# Scale_junction_board.net
KiCad netlist of a schematic drawn in EAGLE
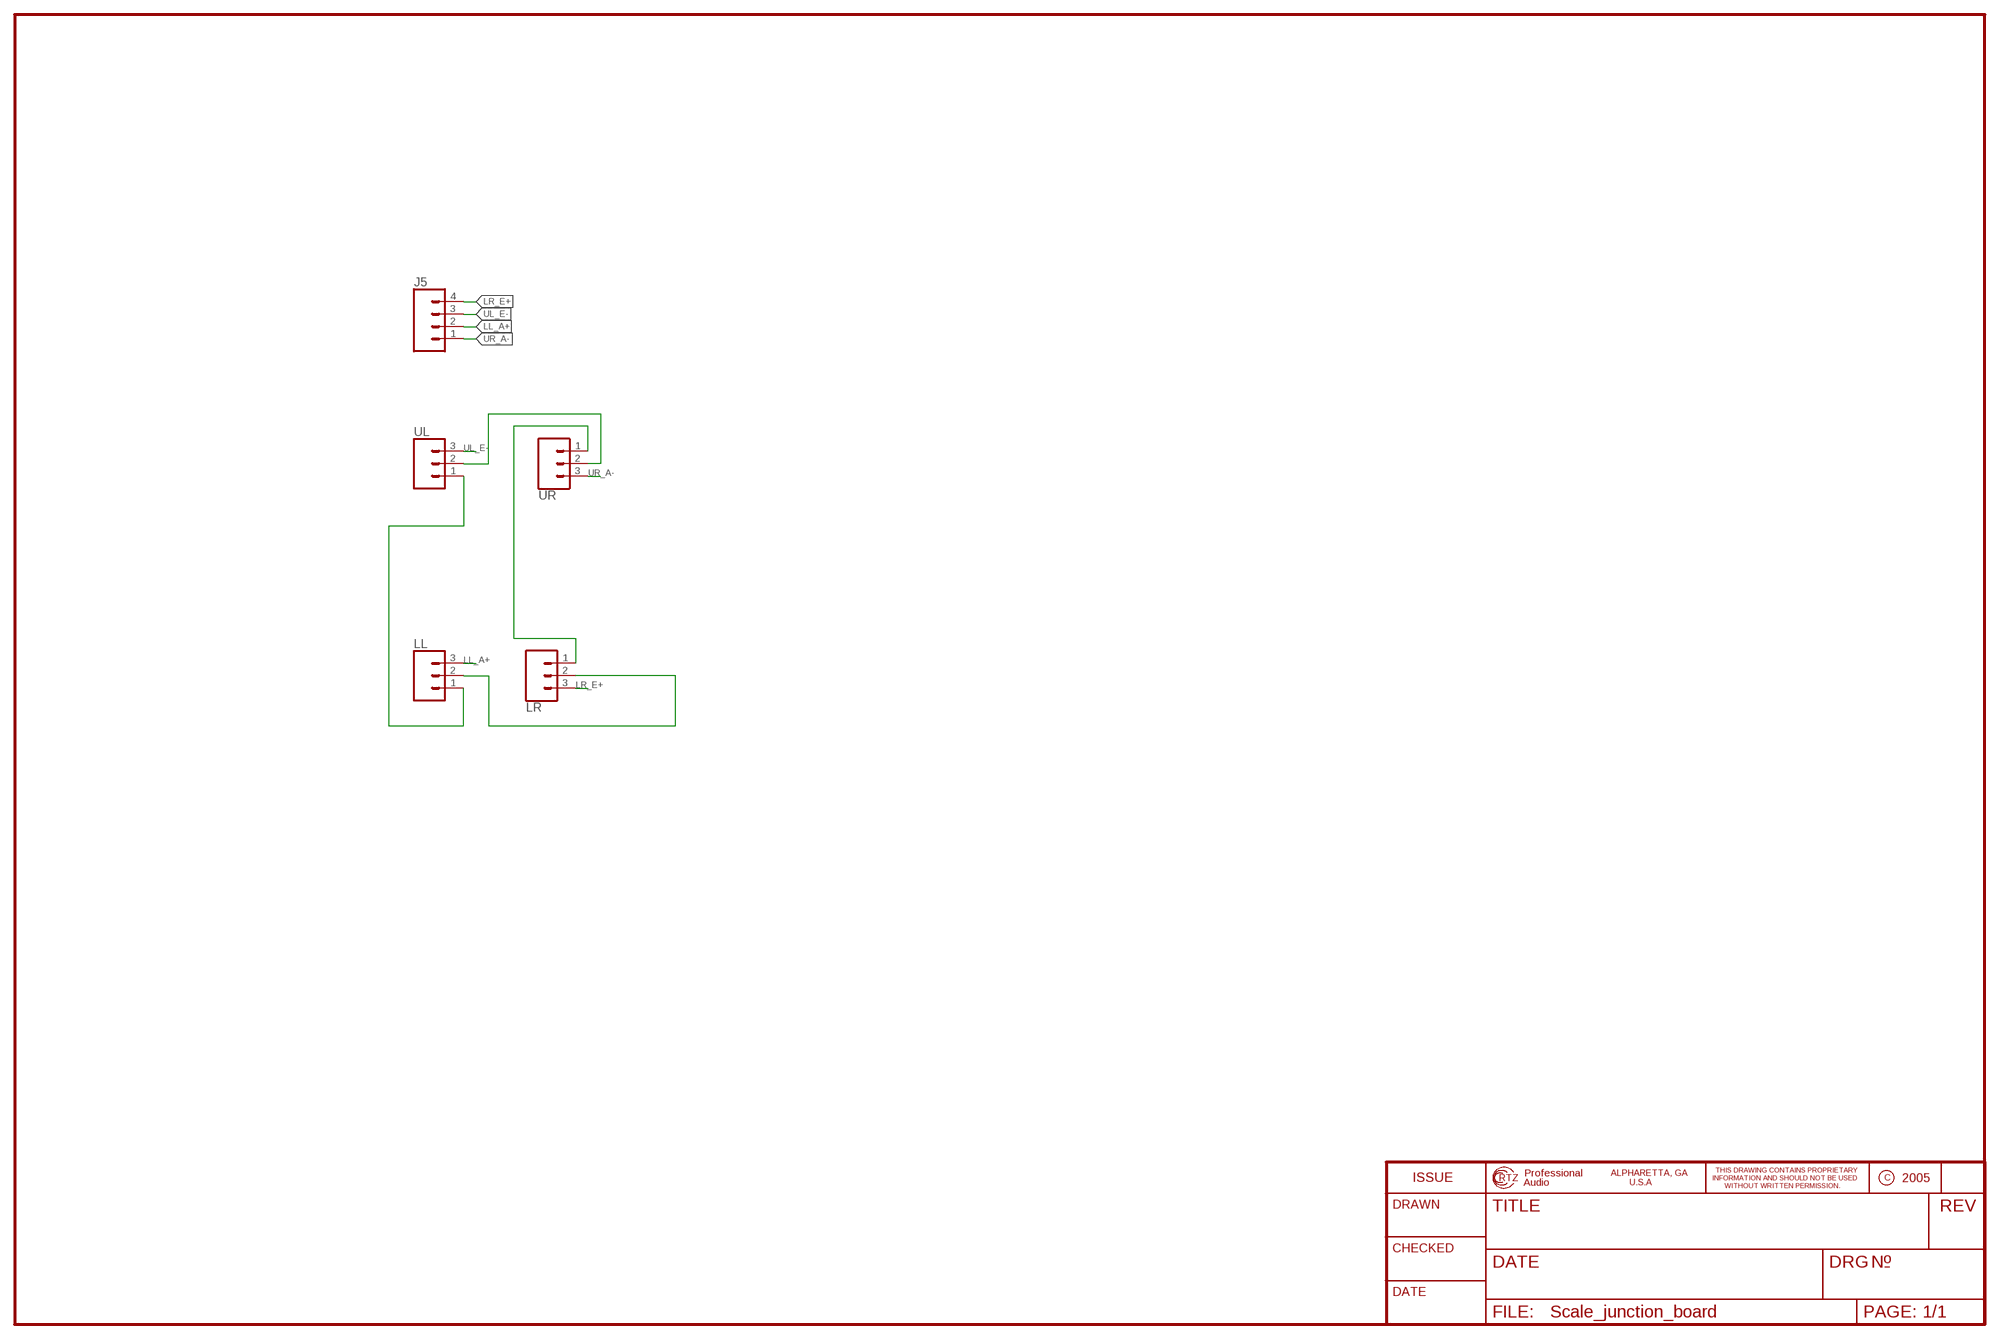
[diagram p0: schematic, sheet 1]

(export (version "E")
  (design (tool "Eeschema 10.0.6"))
  (components
    (comp (ref "J5")
      (value "CONN_04LONGPADS")
      (footprint "eagle-import:1X04_LONGPADS")
      (libsource (lib "eagle-import") (part "CONN_04LONGPADS"))
    )
    (comp (ref "LL")
      (value "CONN_03LONGPADS")
      (footprint "eagle-import:1X03_LONGPADS")
      (libsource (lib "eagle-import") (part "CONN_03LONGPADS"))
    )
    (comp (ref "LR")
      (value "CONN_03LONGPADS")
      (footprint "eagle-import:1X03_LONGPADS")
      (libsource (lib "eagle-import") (part "CONN_03LONGPADS"))
    )
    (comp (ref "UL")
      (value "CONN_03LONGPADS")
      (footprint "eagle-import:1X03_LONGPADS")
      (libsource (lib "eagle-import") (part "CONN_03LONGPADS"))
    )
    (comp (ref "UR")
      (value "CONN_03LONGPADS")
      (footprint "eagle-import:1X03_LONGPADS")
      (libsource (lib "eagle-import") (part "CONN_03LONGPADS"))
    )
  )
  (nets
    (net (code "1") (name "LL_A+") (class "Default")
      (node (ref "J5") (pin "2") (pinfunction "2_2") (pintype "passive"))
      (node (ref "LL") (pin "3") (pinfunction "3_3") (pintype "passive"))
    )
    (net (code "2") (name "LR_E+") (class "Default")
      (node (ref "J5") (pin "4") (pinfunction "4_4") (pintype "passive"))
      (node (ref "LR") (pin "3") (pinfunction "3_3") (pintype "passive"))
    )
    (net (code "3") (name "Net-(LL-Pad1)") (class "Default")
      (node (ref "LL") (pin "1") (pinfunction "1_1") (pintype "passive"))
      (node (ref "UL") (pin "1") (pinfunction "1_1") (pintype "passive"))
    )
    (net (code "4") (name "Net-(LL-Pad2)") (class "Default")
      (node (ref "LL") (pin "2") (pinfunction "2_2") (pintype "passive"))
      (node (ref "LR") (pin "2") (pinfunction "2_2") (pintype "passive"))
    )
    (net (code "5") (name "Net-(LR-Pad1)") (class "Default")
      (node (ref "LR") (pin "1") (pinfunction "1_1") (pintype "passive"))
      (node (ref "UR") (pin "1") (pinfunction "1_1") (pintype "passive"))
    )
    (net (code "6") (name "Net-(UL-Pad2)") (class "Default")
      (node (ref "UL") (pin "2") (pinfunction "2_2") (pintype "passive"))
      (node (ref "UR") (pin "2") (pinfunction "2_2") (pintype "passive"))
    )
    (net (code "7") (name "UL_E-") (class "Default")
      (node (ref "J5") (pin "3") (pinfunction "3_3") (pintype "passive"))
      (node (ref "UL") (pin "3") (pinfunction "3_3") (pintype "passive"))
    )
    (net (code "8") (name "UR_A-") (class "Default")
      (node (ref "J5") (pin "1") (pinfunction "1_1") (pintype "passive"))
      (node (ref "UR") (pin "3") (pinfunction "3_3") (pintype "passive"))
    )
  )
)
